# STM32.net
KiCad netlist of a schematic drawn in Altium Designer
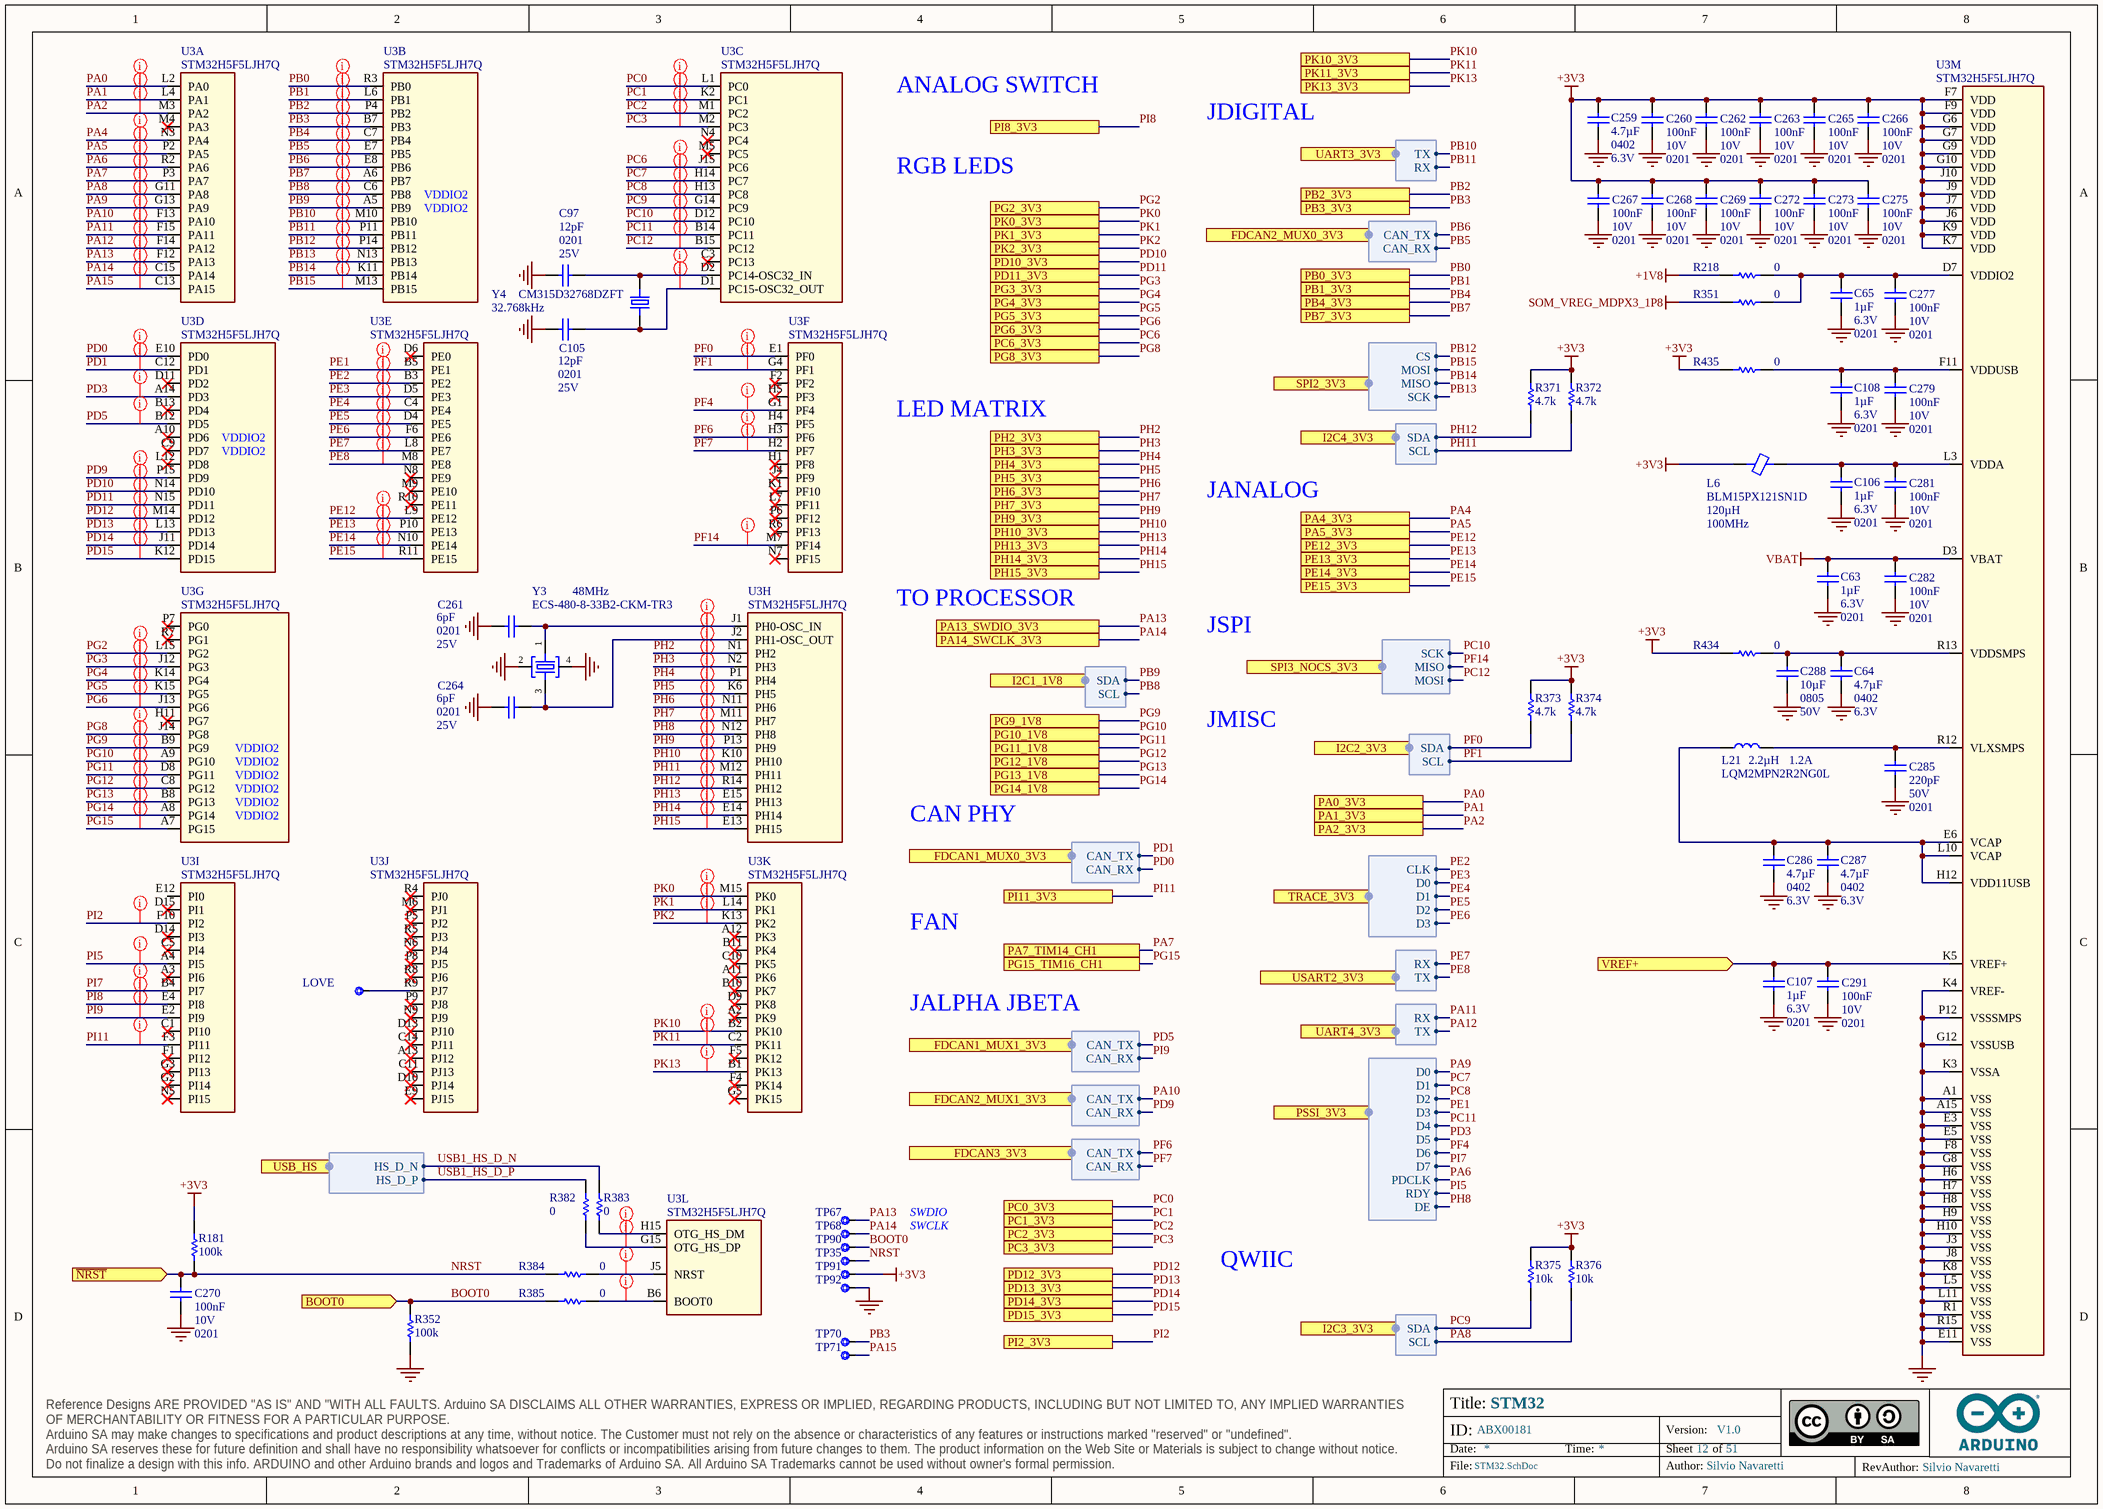
[diagram p0: STM32.SchDoc]

(export (version "E")
  (design (tool "Eeschema 10.0.6"))
  (components
    (comp (ref "C63")
      (value "1µF")
      (footprint "CAP-0201")
      (description "CAP CHIP 0201 1uF 20% 6.3V X5R")
      (fields
        (field (name "VOLTAGE") "6.3V")
        (field (name "TOLERANCE") "20%")
        (field (name "PART NUMBER") "GRM033R60J105MEA2D")
        (field (name "CASE CODE (IMPERIAL)") "0201")
      )
      (libsource (lib "Clean") (part "CAP"))
    )
    (comp (ref "C64")
      (value "4.7µF")
      (footprint "CAP-0402")
      (description "CAP CHIP 0402 4.7uF 20% 6V3 X5R")
      (fields
        (field (name "MANUFACTURER") "Hottech")
        (field (name "PART NUMBER") "C1005A475M6R3NT")
        (field (name "CASE CODE (IMPERIAL)") "0402")
        (field (name "VOLTAGE") "6.3V")
      )
      (libsource (lib "Clean") (part "CAP"))
    )
    (comp (ref "C65")
      (value "1µF")
      (footprint "CAP-0201")
      (description "CAP CHIP 0201 1uF 20% 6.3V X5R")
      (fields
        (field (name "VOLTAGE") "6.3V")
        (field (name "TOLERANCE") "20%")
        (field (name "PART NUMBER") "GRM033R60J105MEA2D")
        (field (name "CASE CODE (IMPERIAL)") "0201")
      )
      (libsource (lib "Clean") (part "CAP"))
    )
    (comp (ref "C97")
      (value "12pF")
      (footprint "CAP-0201")
      (description "CAP CHIP 0201 12pF 5% 25V C0G")
      (fields
        (field (name "CASE CODE (IMPERIAL)") "0201")
        (field (name "PART NUMBER") "GRM0335C1E120JA01J")
        (field (name "VOLTAGE") "25V")
        (field (name "TOLERANCE") "5%")
      )
      (libsource (lib "Clean") (part "CAP"))
    )
    (comp (ref "C105")
      (value "12pF")
      (footprint "CAP-0201")
      (description "CAP CHIP 0201 12pF 5% 25V C0G")
      (fields
        (field (name "CASE CODE (IMPERIAL)") "0201")
        (field (name "PART NUMBER") "GRM0335C1E120JA01J")
        (field (name "VOLTAGE") "25V")
        (field (name "TOLERANCE") "5%")
      )
      (libsource (lib "Clean") (part "CAP"))
    )
    (comp (ref "C106")
      (value "1µF")
      (footprint "CAP-0201")
      (description "CAP CHIP 0201 1uF 20% 6.3V X5R")
      (fields
        (field (name "VOLTAGE") "6.3V")
        (field (name "TOLERANCE") "20%")
        (field (name "PART NUMBER") "GRM033R60J105MEA2D")
        (field (name "CASE CODE (IMPERIAL)") "0201")
      )
      (libsource (lib "Clean") (part "CAP"))
    )
    (comp (ref "C107")
      (value "1µF")
      (footprint "CAP-0201")
      (description "CAP CHIP 0201 1uF 20% 6.3V X5R")
      (fields
        (field (name "VOLTAGE") "6.3V")
        (field (name "TOLERANCE") "20%")
        (field (name "PART NUMBER") "GRM033R60J105MEA2D")
        (field (name "CASE CODE (IMPERIAL)") "0201")
      )
      (libsource (lib "Clean") (part "CAP"))
    )
    (comp (ref "C108")
      (value "1µF")
      (footprint "CAP-0201")
      (description "CAP CHIP 0201 1uF 20% 6.3V X5R")
      (fields
        (field (name "VOLTAGE") "6.3V")
        (field (name "TOLERANCE") "20%")
        (field (name "PART NUMBER") "GRM033R60J105MEA2D")
        (field (name "CASE CODE (IMPERIAL)") "0201")
      )
      (libsource (lib "Clean") (part "CAP"))
    )
    (comp (ref "C259")
      (value "4.7µF")
      (footprint "CAP-0402")
      (description "CAP CHIP 0402 4.7uF 20% 6V3 X5R")
      (fields
        (field (name "MANUFACTURER") "Hottech")
        (field (name "PART NUMBER") "C1005A475M6R3NT")
        (field (name "CASE CODE (IMPERIAL)") "0402")
        (field (name "VOLTAGE") "6.3V")
      )
      (libsource (lib "Clean") (part "CAP"))
    )
    (comp (ref "C260")
      (value "100nF")
      (footprint "CAP-0201")
      (description "CAP CHIP 0201 100nF 10% 10V X5R")
      (fields
        (field (name "PART NUMBER") "CL03A104KP3NNNC")
        (field (name "MANUFACTURER") "Samsung Electro-Mechanics")
        (field (name "VOLTAGE") "10V")
        (field (name "CASE CODE (IMPERIAL)") "0201")
      )
      (libsource (lib "Clean") (part "CAP"))
    )
    (comp (ref "C261")
      (value "6pF")
      (footprint "CAP-0201")
      (description "CAP CHIP 0201 6pF 0.25pF 25V C0G")
      (fields
        (field (name "CASE CODE (IMPERIAL)") "0201")
        (field (name "PART NUMBER") "GRM0335C1E6R0CA01D")
        (field (name "VOLTAGE") "25V")
        (field (name "TOLERANCE") "0.25pF")
      )
      (libsource (lib "Clean") (part "CAP"))
    )
    (comp (ref "C262")
      (value "100nF")
      (footprint "CAP-0201")
      (description "CAP CHIP 0201 100nF 10% 10V X5R")
      (fields
        (field (name "PART NUMBER") "CL03A104KP3NNNC")
        (field (name "MANUFACTURER") "Samsung Electro-Mechanics")
        (field (name "VOLTAGE") "10V")
        (field (name "CASE CODE (IMPERIAL)") "0201")
      )
      (libsource (lib "Clean") (part "CAP"))
    )
    (comp (ref "C263")
      (value "100nF")
      (footprint "CAP-0201")
      (description "CAP CHIP 0201 100nF 10% 10V X5R")
      (fields
        (field (name "PART NUMBER") "CL03A104KP3NNNC")
        (field (name "MANUFACTURER") "Samsung Electro-Mechanics")
        (field (name "VOLTAGE") "10V")
        (field (name "CASE CODE (IMPERIAL)") "0201")
      )
      (libsource (lib "Clean") (part "CAP"))
    )
    (comp (ref "C264")
      (value "6pF")
      (footprint "CAP-0201")
      (description "CAP CHIP 0201 6pF 0.25pF 25V C0G")
      (fields
        (field (name "CASE CODE (IMPERIAL)") "0201")
        (field (name "PART NUMBER") "GRM0335C1E6R0CA01D")
        (field (name "VOLTAGE") "25V")
        (field (name "TOLERANCE") "0.25pF")
      )
      (libsource (lib "Clean") (part "CAP"))
    )
    (comp (ref "C265")
      (value "100nF")
      (footprint "CAP-0201")
      (description "CAP CHIP 0201 100nF 10% 10V X5R")
      (fields
        (field (name "PART NUMBER") "CL03A104KP3NNNC")
        (field (name "MANUFACTURER") "Samsung Electro-Mechanics")
        (field (name "VOLTAGE") "10V")
        (field (name "CASE CODE (IMPERIAL)") "0201")
      )
      (libsource (lib "Clean") (part "CAP"))
    )
    (comp (ref "C266")
      (value "100nF")
      (footprint "CAP-0201")
      (description "CAP CHIP 0201 100nF 10% 10V X5R")
      (fields
        (field (name "PART NUMBER") "CL03A104KP3NNNC")
        (field (name "MANUFACTURER") "Samsung Electro-Mechanics")
        (field (name "VOLTAGE") "10V")
        (field (name "CASE CODE (IMPERIAL)") "0201")
      )
      (libsource (lib "Clean") (part "CAP"))
    )
    (comp (ref "C267")
      (value "100nF")
      (footprint "CAP-0201")
      (description "CAP CHIP 0201 100nF 10% 10V X5R")
      (fields
        (field (name "PART NUMBER") "CL03A104KP3NNNC")
        (field (name "MANUFACTURER") "Samsung Electro-Mechanics")
        (field (name "VOLTAGE") "10V")
        (field (name "CASE CODE (IMPERIAL)") "0201")
      )
      (libsource (lib "Clean") (part "CAP"))
    )
    (comp (ref "C268")
      (value "100nF")
      (footprint "CAP-0201")
      (description "CAP CHIP 0201 100nF 10% 10V X5R")
      (fields
        (field (name "PART NUMBER") "CL03A104KP3NNNC")
        (field (name "MANUFACTURER") "Samsung Electro-Mechanics")
        (field (name "VOLTAGE") "10V")
        (field (name "CASE CODE (IMPERIAL)") "0201")
      )
      (libsource (lib "Clean") (part "CAP"))
    )
    (comp (ref "C269")
      (value "100nF")
      (footprint "CAP-0201")
      (description "CAP CHIP 0201 100nF 10% 10V X5R")
      (fields
        (field (name "PART NUMBER") "CL03A104KP3NNNC")
        (field (name "MANUFACTURER") "Samsung Electro-Mechanics")
        (field (name "VOLTAGE") "10V")
        (field (name "CASE CODE (IMPERIAL)") "0201")
      )
      (libsource (lib "Clean") (part "CAP"))
    )
    (comp (ref "C270")
      (value "100nF")
      (footprint "CAP-0201")
      (description "CAP CHIP 0201 100nF 10% 10V X5R")
      (fields
        (field (name "PART NUMBER") "CL03A104KP3NNNC")
        (field (name "MANUFACTURER") "Samsung Electro-Mechanics")
        (field (name "VOLTAGE") "10V")
        (field (name "CASE CODE (IMPERIAL)") "0201")
      )
      (libsource (lib "Clean") (part "CAP"))
    )
    (comp (ref "C272")
      (value "100nF")
      (footprint "CAP-0201")
      (description "CAP CHIP 0201 100nF 10% 10V X5R")
      (fields
        (field (name "PART NUMBER") "CL03A104KP3NNNC")
        (field (name "MANUFACTURER") "Samsung Electro-Mechanics")
        (field (name "VOLTAGE") "10V")
        (field (name "CASE CODE (IMPERIAL)") "0201")
      )
      (libsource (lib "Clean") (part "CAP"))
    )
    (comp (ref "C273")
      (value "100nF")
      (footprint "CAP-0201")
      (description "CAP CHIP 0201 100nF 10% 10V X5R")
      (fields
        (field (name "PART NUMBER") "CL03A104KP3NNNC")
        (field (name "MANUFACTURER") "Samsung Electro-Mechanics")
        (field (name "VOLTAGE") "10V")
        (field (name "CASE CODE (IMPERIAL)") "0201")
      )
      (libsource (lib "Clean") (part "CAP"))
    )
    (comp (ref "C275")
      (value "100nF")
      (footprint "CAP-0201")
      (description "CAP CHIP 0201 100nF 10% 10V X5R")
      (fields
        (field (name "PART NUMBER") "CL03A104KP3NNNC")
        (field (name "MANUFACTURER") "Samsung Electro-Mechanics")
        (field (name "VOLTAGE") "10V")
        (field (name "CASE CODE (IMPERIAL)") "0201")
      )
      (libsource (lib "Clean") (part "CAP"))
    )
    (comp (ref "C277")
      (value "100nF")
      (footprint "CAP-0201")
      (description "CAP CHIP 0201 100nF 10% 10V X5R")
      (fields
        (field (name "PART NUMBER") "CL03A104KP3NNNC")
        (field (name "MANUFACTURER") "Samsung Electro-Mechanics")
        (field (name "VOLTAGE") "10V")
        (field (name "CASE CODE (IMPERIAL)") "0201")
      )
      (libsource (lib "Clean") (part "CAP"))
    )
    (comp (ref "C279")
      (value "100nF")
      (footprint "CAP-0201")
      (description "CAP CHIP 0201 100nF 10% 10V X5R")
      (fields
        (field (name "PART NUMBER") "CL03A104KP3NNNC")
        (field (name "MANUFACTURER") "Samsung Electro-Mechanics")
        (field (name "VOLTAGE") "10V")
        (field (name "CASE CODE (IMPERIAL)") "0201")
      )
      (libsource (lib "Clean") (part "CAP"))
    )
    (comp (ref "C281")
      (value "100nF")
      (footprint "CAP-0201")
      (description "CAP CHIP 0201 100nF 10% 10V X5R")
      (fields
        (field (name "PART NUMBER") "CL03A104KP3NNNC")
        (field (name "MANUFACTURER") "Samsung Electro-Mechanics")
        (field (name "VOLTAGE") "10V")
        (field (name "CASE CODE (IMPERIAL)") "0201")
      )
      (libsource (lib "Clean") (part "CAP"))
    )
    (comp (ref "C282")
      (value "100nF")
      (footprint "CAP-0201")
      (description "CAP CHIP 0201 100nF 10% 10V X5R")
      (fields
        (field (name "PART NUMBER") "CL03A104KP3NNNC")
        (field (name "MANUFACTURER") "Samsung Electro-Mechanics")
        (field (name "VOLTAGE") "10V")
        (field (name "CASE CODE (IMPERIAL)") "0201")
      )
      (libsource (lib "Clean") (part "CAP"))
    )
    (comp (ref "C285")
      (value "220pF")
      (footprint "CAP-0201")
      (description "CAP CHIP 0201 220pF 10% 50V X7R")
      (fields
        (field (name "PART NUMBER") "GRM033R71H221KA12D")
        (field (name "MANUFACTURER") "Murata")
        (field (name "VOLTAGE") "50V")
        (field (name "CASE CODE (IMPERIAL)") "0201")
      )
      (libsource (lib "Clean") (part "CAP"))
    )
    (comp (ref "C286")
      (value "4.7µF")
      (footprint "CAP-0402")
      (description "CAP CHIP 0402 4.7uF 20% 6V3 X5R")
      (fields
        (field (name "MANUFACTURER") "Hottech")
        (field (name "PART NUMBER") "C1005A475M6R3NT")
        (field (name "CASE CODE (IMPERIAL)") "0402")
        (field (name "VOLTAGE") "6.3V")
      )
      (libsource (lib "Clean") (part "CAP"))
    )
    (comp (ref "C287")
      (value "4.7µF")
      (footprint "CAP-0402")
      (description "CAP CHIP 0402 4.7uF 20% 6V3 X5R")
      (fields
        (field (name "MANUFACTURER") "Hottech")
        (field (name "PART NUMBER") "C1005A475M6R3NT")
        (field (name "CASE CODE (IMPERIAL)") "0402")
        (field (name "VOLTAGE") "6.3V")
      )
      (libsource (lib "Clean") (part "CAP"))
    )
    (comp (ref "C288")
      (value "10µF")
      (footprint "CAP-0805")
      (description "CAP CHIP 0805 10uF 20% 50V X5R")
      (fields
        (field (name "CASE CODE (IMPERIAL)") "0805")
        (field (name "TOLERANCE") "20%")
        (field (name "PART NUMBER") "GRM21BR61H106ME43L")
        (field (name "VOLTAGE") "50V")
      )
      (libsource (lib "Clean") (part "CAP"))
    )
    (comp (ref "C291")
      (value "100nF")
      (footprint "CAP-0201")
      (description "CAP CHIP 0201 100nF 10% 10V X5R")
      (fields
        (field (name "PART NUMBER") "CL03A104KP3NNNC")
        (field (name "MANUFACTURER") "Samsung Electro-Mechanics")
        (field (name "VOLTAGE") "10V")
        (field (name "CASE CODE (IMPERIAL)") "0201")
      )
      (libsource (lib "Clean") (part "CAP"))
    )
    (comp (ref "L6")
      (value "BLM15PX121SN1D")
      (footprint "L-0402")
      (description "FERRITE SMD 0402 120Ohm 25% 100MHz Ferrite 2A")
      (fields
        (field (name "INDUCTANCE") "120µH")
        (field (name "TEST FREQUENCY") "100MHz")
        (field (name "MANUFACTURER") "Murata")
        (field (name "TOLERANCE") "25%")
      )
      (libsource (lib "Clean") (part "Ferrite"))
    )
    (comp (ref "L21")
      (value "LQM2MPN2R2NG0L")
      (footprint "LQM2MPN2R2NG0L")
      (description "INDUCTOR SMD 0806 2.2uH 1.2A")
      (fields
        (field (name "CURRENT") "1.2A")
        (field (name "INDUCTANCE") "2.2µH")
        (field (name "TOLERANCE") "30%")
        (field (name "MANUFACTURER") "Murata")
      )
      (libsource (lib "Clean") (part "Inductor"))
    )
    (comp (ref "LOVE")
      (value "Test point 1.00mm")
      (footprint "TP-1.00MM")
      (fields (field (name "MANUFACTURER") "This is not a component"))
      (libsource (lib "Clean") (part "TESTPOINT"))
    )
    (comp (ref "R181")
      (value "100k")
      (footprint "RES-0201")
      (description "RES CHIP 0201 100k 1% 1/20W")
      (fields (field (name "POWER") "50mW") (field (name "TOLERANCE") "1%"))
      (libsource (lib "Clean") (part "RES"))
    )
    (comp (ref "R218")
      (value "0")
      (footprint "RES-0201")
      (description "RES CHIP 0201 0R")
      (fields (field (name "MANUFACTURER") "Vishay") (field (name "PART NUMBER") "CRCW02010000Z0ED"))
      (libsource (lib "Clean") (part "RES"))
    )
    (comp (ref "R351")
      (value "0")
      (footprint "RES-0201")
      (description "RES CHIP 0201 0R")
      (fields (field (name "MANUFACTURER") "Vishay") (field (name "PART NUMBER") "CRCW02010000Z0ED"))
      (libsource (lib "Clean") (part "RES"))
    )
    (comp (ref "R352")
      (value "100k")
      (footprint "RES-0201")
      (description "RES CHIP 0201 100k 1% 1/20W")
      (fields (field (name "POWER") "50mW") (field (name "TOLERANCE") "1%"))
      (libsource (lib "Clean") (part "RES"))
    )
    (comp (ref "R371")
      (value "4.7k")
      (footprint "RES-0201")
      (description "RES CHIP 0201 4k7 1% 1/20W")
      (fields (field (name "POWER") "50mW") (field (name "TOLERANCE") "1%"))
      (libsource (lib "Clean") (part "RES"))
    )
    (comp (ref "R372")
      (value "4.7k")
      (footprint "RES-0201")
      (description "RES CHIP 0201 4k7 1% 1/20W")
      (fields (field (name "POWER") "50mW") (field (name "TOLERANCE") "1%"))
      (libsource (lib "Clean") (part "RES"))
    )
    (comp (ref "R373")
      (value "4.7k")
      (footprint "RES-0201")
      (description "RES CHIP 0201 4k7 1% 1/20W")
      (fields (field (name "POWER") "50mW") (field (name "TOLERANCE") "1%"))
      (libsource (lib "Clean") (part "RES"))
    )
    (comp (ref "R374")
      (value "4.7k")
      (footprint "RES-0201")
      (description "RES CHIP 0201 4k7 1% 1/20W")
      (fields (field (name "POWER") "50mW") (field (name "TOLERANCE") "1%"))
      (libsource (lib "Clean") (part "RES"))
    )
    (comp (ref "R375")
      (value "10k")
      (footprint "RES-0201")
      (description "RES CHIP 0201 10k 1% 1/20W")
      (fields (field (name "POWER") "50mW") (field (name "TOLERANCE") "1%"))
      (libsource (lib "Clean") (part "RES"))
    )
    (comp (ref "R376")
      (value "10k")
      (footprint "RES-0201")
      (description "RES CHIP 0201 10k 1% 1/20W")
      (fields (field (name "POWER") "50mW") (field (name "TOLERANCE") "1%"))
      (libsource (lib "Clean") (part "RES"))
    )
    (comp (ref "R382")
      (value "0")
      (footprint "RES-0201")
      (description "RES CHIP 0201 0R")
      (fields (field (name "MANUFACTURER") "Vishay") (field (name "PART NUMBER") "CRCW02010000Z0ED"))
      (libsource (lib "Clean") (part "RES"))
    )
    (comp (ref "R383")
      (value "0")
      (footprint "RES-0201")
      (description "RES CHIP 0201 0R")
      (fields (field (name "MANUFACTURER") "Vishay") (field (name "PART NUMBER") "CRCW02010000Z0ED"))
      (libsource (lib "Clean") (part "RES"))
    )
    (comp (ref "R384")
      (value "0")
      (footprint "RES-0201")
      (description "RES CHIP 0201 0R")
      (fields (field (name "MANUFACTURER") "Vishay") (field (name "PART NUMBER") "CRCW02010000Z0ED"))
      (libsource (lib "Clean") (part "RES"))
    )
    (comp (ref "R385")
      (value "0")
      (footprint "RES-0201")
      (description "RES CHIP 0201 0R")
      (fields (field (name "MANUFACTURER") "Vishay") (field (name "PART NUMBER") "CRCW02010000Z0ED"))
      (libsource (lib "Clean") (part "RES"))
    )
    (comp (ref "R434")
      (value "0")
      (footprint "RES-0201")
      (description "RES CHIP 0201 0R")
      (fields (field (name "MANUFACTURER") "Vishay") (field (name "PART NUMBER") "CRCW02010000Z0ED"))
      (libsource (lib "Clean") (part "RES"))
    )
    (comp (ref "R435")
      (value "0")
      (footprint "RES-0201")
      (description "RES CHIP 0201 0R")
      (fields (field (name "MANUFACTURER") "Vishay") (field (name "PART NUMBER") "CRCW02010000Z0ED"))
      (libsource (lib "Clean") (part "RES"))
    )
    (comp (ref "TP35")
      (value "Test point 1.00mm")
      (footprint "TP-1.00MM")
      (fields (field (name "PART NUMBER") "This is not a component"))
      (libsource (lib "Clean") (part "TESTPOINT"))
    )
    (comp (ref "TP67")
      (value "Test point 1.00mm")
      (footprint "TP-1.00MM")
      (fields (field (name "PART NUMBER") "This is not a component"))
      (libsource (lib "Clean") (part "TESTPOINT"))
    )
    (comp (ref "TP68")
      (value "Test point 1.00mm")
      (footprint "TP-1.00MM")
      (fields (field (name "PART NUMBER") "This is not a component"))
      (libsource (lib "Clean") (part "TESTPOINT"))
    )
    (comp (ref "TP70")
      (value "Test point 1.00mm")
      (footprint "TP-1.00MM")
      (fields (field (name "PART NUMBER") "This is not a component"))
      (libsource (lib "Clean") (part "TESTPOINT"))
    )
    (comp (ref "TP71")
      (value "Test point 1.00mm")
      (footprint "TP-1.00MM")
      (fields (field (name "PART NUMBER") "This is not a component"))
      (libsource (lib "Clean") (part "TESTPOINT"))
    )
    (comp (ref "TP90")
      (value "Test point 1.00mm")
      (footprint "TP-1.00MM")
      (fields (field (name "PART NUMBER") "This is not a component"))
      (libsource (lib "Clean") (part "TESTPOINT"))
    )
    (comp (ref "TP91")
      (value "Test point 1.00mm")
      (footprint "TP-1.00MM")
      (fields (field (name "PART NUMBER") "This is not a component"))
      (libsource (lib "Clean") (part "TESTPOINT"))
    )
    (comp (ref "TP92")
      (value "Test point 1.00mm")
      (footprint "TP-1.00MM")
      (fields (field (name "PART NUMBER") "This is not a component"))
      (libsource (lib "Clean") (part "TESTPOINT"))
    )
    (comp (ref "U3")
      (value "STM32H5F5LJH7Q")
      (footprint "BGA225C80P15X15_1300X1300X120")
      (description "IC Cortex M33 250MHz, 4MB flash, 1.5MB RAM, TFBGA225 13x13mm")
      (fields (field (name "MANUFACTURER") "ST"))
      (libsource (lib "Clean") (part "STM32H5F5LJH7Q"))
    )
    (comp (ref "Y3")
      (value "ECS-480-8-33B2-CKM-TR3")
      (footprint "CRYSTAL3.2X2.5")
      (description "CRYSTAL 48MHz tolerance 10ppm stability 15ppm load 10pF, shunt 2pF, ESR 30R, 3.2x2.5mm")
      (fields (field (name "FREQUENCY") "48MHz") (field (name "MANUFACTURER") "ECS"))
      (libsource (lib "Clean") (part "Crystal"))
    )
    (comp (ref "Y4")
      (value "CM315D32768DZFT")
      (footprint "ABS07")
      (description "CRYSTAL 32.768kHz 20ppm 12.5pF SMD 1.6x0.9mm")
      (fields (field (name "FREQUENCY") "32.768kHz") (field (name "MANUFACTURER") "Citizen FineDevice"))
      (libsource (lib "") (part "Crystal_1"))
    )
  )
  (nets
    (net (code "9") (name "+1V8") (class "Default")
      (node (ref "R218") (pin "1") (pinfunction "1_1") (pintype "passive"))
    )
    (net (code "10") (name "+3V3") (class "Default")
      (node (ref "C259") (pin "1") (pinfunction "1_1") (pintype "passive"))
      (node (ref "C260") (pin "2") (pinfunction "2_2") (pintype "passive"))
      (node (ref "C262") (pin "2") (pinfunction "2_2") (pintype "passive"))
      (node (ref "C263") (pin "2") (pinfunction "2_2") (pintype "passive"))
      (node (ref "C265") (pin "2") (pinfunction "2_2") (pintype "passive"))
      (node (ref "C266") (pin "2") (pinfunction "2_2") (pintype "passive"))
      (node (ref "C267") (pin "2") (pinfunction "2_2") (pintype "passive"))
      (node (ref "C268") (pin "2") (pinfunction "2_2") (pintype "passive"))
      (node (ref "C269") (pin "2") (pinfunction "2_2") (pintype "passive"))
      (node (ref "C272") (pin "2") (pinfunction "2_2") (pintype "passive"))
      (node (ref "C273") (pin "2") (pinfunction "2_2") (pintype "passive"))
      (node (ref "C275") (pin "2") (pinfunction "2_2") (pintype "passive"))
      (node (ref "L6") (pin "1") (pinfunction "1_1") (pintype "passive"))
      (node (ref "R181") (pin "2") (pinfunction "2_2") (pintype "passive"))
      (node (ref "R371") (pin "2") (pinfunction "2_2") (pintype "passive"))
      (node (ref "R372") (pin "2") (pinfunction "2_2") (pintype "passive"))
      (node (ref "R373") (pin "2") (pinfunction "2_2") (pintype "passive"))
      (node (ref "R374") (pin "2") (pinfunction "2_2") (pintype "passive"))
      (node (ref "R375") (pin "2") (pinfunction "2_2") (pintype "passive"))
      (node (ref "R376") (pin "2") (pinfunction "2_2") (pintype "passive"))
      (node (ref "R434") (pin "1") (pinfunction "1_1") (pintype "passive"))
      (node (ref "R435") (pin "1") (pinfunction "1_1") (pintype "passive"))
      (node (ref "TP91") (pin "X") (pinfunction "X_X") (pintype "passive"))
      (node (ref "U3") (pin "F7") (pinfunction "VDD_F7") (pintype "passive"))
      (node (ref "U3") (pin "F9") (pinfunction "VDD_F9") (pintype "passive"))
      (node (ref "U3") (pin "G10") (pinfunction "VDD_G10") (pintype "passive"))
      (node (ref "U3") (pin "G6") (pinfunction "VDD_G6") (pintype "passive"))
      (node (ref "U3") (pin "G7") (pinfunction "VDD_G7") (pintype "passive"))
      (node (ref "U3") (pin "G9") (pinfunction "VDD_G9") (pintype "passive"))
      (node (ref "U3") (pin "J10") (pinfunction "VDD_J10") (pintype "passive"))
      (node (ref "U3") (pin "J6") (pinfunction "VDD_J6") (pintype "passive"))
      (node (ref "U3") (pin "J7") (pinfunction "VDD_J7") (pintype "passive"))
      (node (ref "U3") (pin "J9") (pinfunction "VDD_J9") (pintype "passive"))
      (node (ref "U3") (pin "K7") (pinfunction "VDD_K7") (pintype "passive"))
      (node (ref "U3") (pin "K9") (pinfunction "VDD_K9") (pintype "passive"))
    )
    (net (code "11") (name "/BOOT0") (class "Default")
      (node (ref "R352") (pin "2") (pinfunction "2_2") (pintype "passive"))
      (node (ref "R385") (pin "1") (pinfunction "1_1") (pintype "passive"))
      (node (ref "TP90") (pin "X") (pinfunction "X_X") (pintype "passive"))
    )
    (net (code "12") (name "/NRST") (class "Default")
      (node (ref "C270") (pin "2") (pinfunction "2_2") (pintype "passive"))
      (node (ref "R181") (pin "1") (pinfunction "1_1") (pintype "passive"))
      (node (ref "R384") (pin "1") (pinfunction "1_1") (pintype "passive"))
      (node (ref "TP35") (pin "X") (pinfunction "X_X") (pintype "passive"))
    )
    (net (code "13") (name "/PA0") (class "Default")
      (node (ref "U3") (pin "L2") (pinfunction "PA0_L2") (pintype "passive"))
    )
    (net (code "14") (name "/PA1") (class "Default")
      (node (ref "U3") (pin "L4") (pinfunction "PA1_L4") (pintype "passive"))
    )
    (net (code "15") (name "/PA2") (class "Default")
      (node (ref "U3") (pin "M3") (pinfunction "PA2_M3") (pintype "passive"))
    )
    (net (code "16") (name "/PA4") (class "Default")
      (node (ref "U3") (pin "N3") (pinfunction "PA4_N3") (pintype "passive"))
    )
    (net (code "17") (name "/PA5") (class "Default")
      (node (ref "U3") (pin "P2") (pinfunction "PA5_P2") (pintype "passive"))
    )
    (net (code "18") (name "/PA6") (class "Default")
      (node (ref "U3") (pin "R2") (pinfunction "PA6_R2") (pintype "passive"))
    )
    (net (code "19") (name "/PA7") (class "Default")
      (node (ref "U3") (pin "P3") (pinfunction "PA7_P3") (pintype "passive"))
    )
    (net (code "20") (name "/PA8") (class "Default")
      (node (ref "R376") (pin "1") (pinfunction "1_1") (pintype "passive"))
      (node (ref "U3") (pin "G11") (pinfunction "PA8_G11") (pintype "passive"))
    )
    (net (code "21") (name "/PA9") (class "Default")
      (node (ref "U3") (pin "G13") (pinfunction "PA9_G13") (pintype "passive"))
    )
    (net (code "22") (name "/PA10") (class "Default")
      (node (ref "U3") (pin "F13") (pinfunction "PA10_F13") (pintype "passive"))
    )
    (net (code "23") (name "/PA11") (class "Default")
      (node (ref "U3") (pin "F15") (pinfunction "PA11_F15") (pintype "passive"))
    )
    (net (code "24") (name "/PA12") (class "Default")
      (node (ref "U3") (pin "F14") (pinfunction "PA12_F14") (pintype "passive"))
    )
    (net (code "25") (name "/PA13") (class "Default")
      (node (ref "TP67") (pin "X") (pinfunction "X_X") (pintype "passive"))
      (node (ref "U3") (pin "F12") (pinfunction "PA13_F12") (pintype "passive"))
    )
    (net (code "26") (name "/PA14") (class "Default")
      (node (ref "TP68") (pin "X") (pinfunction "X_X") (pintype "passive"))
      (node (ref "U3") (pin "C15") (pinfunction "PA14_C15") (pintype "passive"))
    )
    (net (code "27") (name "/PA15") (class "Default")
      (node (ref "TP71") (pin "X") (pinfunction "X_X") (pintype "passive"))
      (node (ref "U3") (pin "C13") (pinfunction "PA15_C13") (pintype "passive"))
    )
    (net (code "28") (name "/PB0") (class "Default")
      (node (ref "U3") (pin "R3") (pinfunction "PB0_R3") (pintype "passive"))
    )
    (net (code "29") (name "/PB1") (class "Default")
      (node (ref "U3") (pin "L6") (pinfunction "PB1_L6") (pintype "passive"))
    )
    (net (code "30") (name "/PB2") (class "Default")
      (node (ref "U3") (pin "P4") (pinfunction "PB2_P4") (pintype "passive"))
    )
    (net (code "31") (name "/PB3") (class "Default")
      (node (ref "TP70") (pin "X") (pinfunction "X_X") (pintype "passive"))
      (node (ref "U3") (pin "B7") (pinfunction "PB3_B7") (pintype "passive"))
    )
    (net (code "32") (name "/PB4") (class "Default")
      (node (ref "U3") (pin "C7") (pinfunction "PB4_C7") (pintype "passive"))
    )
    (net (code "33") (name "/PB5") (class "Default")
      (node (ref "U3") (pin "E7") (pinfunction "PB5_E7") (pintype "passive"))
    )
    (net (code "34") (name "/PB6") (class "Default")
      (node (ref "U3") (pin "E8") (pinfunction "PB6_E8") (pintype "passive"))
    )
    (net (code "35") (name "/PB7") (class "Default")
      (node (ref "U3") (pin "A6") (pinfunction "PB7_A6") (pintype "passive"))
    )
    (net (code "36") (name "/PB8") (class "Default")
      (node (ref "U3") (pin "C6") (pinfunction "PB8_C6") (pintype "passive"))
    )
    (net (code "37") (name "/PB9") (class "Default")
      (node (ref "U3") (pin "A5") (pinfunction "PB9_A5") (pintype "passive"))
    )
    (net (code "38") (name "/PB10") (class "Default")
      (node (ref "U3") (pin "M10") (pinfunction "PB10_M10") (pintype "passive"))
    )
    (net (code "39") (name "/PB11") (class "Default")
      (node (ref "U3") (pin "P11") (pinfunction "PB11_P11") (pintype "passive"))
    )
    (net (code "40") (name "/PB12") (class "Default")
      (node (ref "U3") (pin "P14") (pinfunction "PB12_P14") (pintype "passive"))
    )
    (net (code "41") (name "/PB13") (class "Default")
      (node (ref "U3") (pin "N13") (pinfunction "PB13_N13") (pintype "passive"))
    )
    (net (code "42") (name "/PB14") (class "Default")
      (node (ref "U3") (pin "K11") (pinfunction "PB14_K11") (pintype "passive"))
    )
    (net (code "43") (name "/PB15") (class "Default")
      (node (ref "U3") (pin "M13") (pinfunction "PB15_M13") (pintype "passive"))
    )
    (net (code "44") (name "/PC0") (class "Default")
      (node (ref "U3") (pin "L1") (pinfunction "PC0_L1") (pintype "passive"))
    )
    (net (code "45") (name "/PC1") (class "Default")
      (node (ref "U3") (pin "K2") (pinfunction "PC1_K2") (pintype "passive"))
    )
    (net (code "46") (name "/PC2") (class "Default")
      (node (ref "U3") (pin "M1") (pinfunction "PC2_M1") (pintype "passive"))
    )
    (net (code "47") (name "/PC3") (class "Default")
      (node (ref "U3") (pin "M2") (pinfunction "PC3_M2") (pintype "passive"))
    )
    (net (code "48") (name "/PC6") (class "Default")
      (node (ref "U3") (pin "J15") (pinfunction "PC6_J15") (pintype "passive"))
    )
    (net (code "49") (name "/PC7") (class "Default")
      (node (ref "U3") (pin "H14") (pinfunction "PC7_H14") (pintype "passive"))
    )
    (net (code "50") (name "/PC8") (class "Default")
      (node (ref "U3") (pin "H13") (pinfunction "PC8_H13") (pintype "passive"))
    )
    (net (code "51") (name "/PC9") (class "Default")
      (node (ref "R375") (pin "1") (pinfunction "1_1") (pintype "passive"))
      (node (ref "U3") (pin "G14") (pinfunction "PC9_G14") (pintype "passive"))
    )
    (net (code "52") (name "/PC10") (class "Default")
      (node (ref "U3") (pin "D12") (pinfunction "PC10_D12") (pintype "passive"))
    )
    (net (code "53") (name "/PC11") (class "Default")
      (node (ref "U3") (pin "B14") (pinfunction "PC11_B14") (pintype "passive"))
    )
    (net (code "54") (name "/PC12") (class "Default")
      (node (ref "U3") (pin "B15") (pinfunction "PC12_B15") (pintype "passive"))
    )
    (net (code "55") (name "/PD0") (class "Default")
      (node (ref "U3") (pin "E10") (pinfunction "PD0_E10") (pintype "passive"))
    )
    (net (code "56") (name "/PD1") (class "Default")
      (node (ref "U3") (pin "C12") (pinfunction "PD1_C12") (pintype "passive"))
    )
    (net (code "57") (name "/PD3") (class "Default")
      (node (ref "U3") (pin "A14") (pinfunction "PD3_A14") (pintype "passive"))
    )
    (net (code "58") (name "/PD5") (class "Default")
      (node (ref "U3") (pin "B12") (pinfunction "PD5_B12") (pintype "passive"))
    )
    (net (code "59") (name "/PD9") (class "Default")
      (node (ref "U3") (pin "P15") (pinfunction "PD9_P15") (pintype "passive"))
    )
    (net (code "60") (name "/PD10") (class "Default")
      (node (ref "U3") (pin "N14") (pinfunction "PD10_N14") (pintype "passive"))
    )
    (net (code "61") (name "/PD11") (class "Default")
      (node (ref "U3") (pin "N15") (pinfunction "PD11_N15") (pintype "passive"))
    )
    (net (code "62") (name "/PD12") (class "Default")
      (node (ref "U3") (pin "M14") (pinfunction "PD12_M14") (pintype "passive"))
    )
    (net (code "63") (name "/PD13") (class "Default")
      (node (ref "U3") (pin "L13") (pinfunction "PD13_L13") (pintype "passive"))
    )
    (net (code "64") (name "/PD14") (class "Default")
      (node (ref "U3") (pin "J11") (pinfunction "PD14_J11") (pintype "passive"))
    )
    (net (code "65") (name "/PD15") (class "Default")
      (node (ref "U3") (pin "K12") (pinfunction "PD15_K12") (pintype "passive"))
    )
    (net (code "66") (name "/PE1") (class "Default")
      (node (ref "U3") (pin "B5") (pinfunction "PE1_B5") (pintype "passive"))
    )
    (net (code "67") (name "/PE2") (class "Default")
      (node (ref "U3") (pin "B3") (pinfunction "PE2_B3") (pintype "passive"))
    )
    (net (code "68") (name "/PE3") (class "Default")
      (node (ref "U3") (pin "D5") (pinfunction "PE3_D5") (pintype "passive"))
    )
    (net (code "69") (name "/PE4") (class "Default")
      (node (ref "U3") (pin "C4") (pinfunction "PE4_C4") (pintype "passive"))
    )
    (net (code "70") (name "/PE5") (class "Default")
      (node (ref "U3") (pin "D4") (pinfunction "PE5_D4") (pintype "passive"))
    )
    (net (code "71") (name "/PE6") (class "Default")
      (node (ref "U3") (pin "F6") (pinfunction "PE6_F6") (pintype "passive"))
    )
    (net (code "72") (name "/PE7") (class "Default")
      (node (ref "U3") (pin "L8") (pinfunction "PE7_L8") (pintype "passive"))
    )
    (net (code "73") (name "/PE8") (class "Default")
      (node (ref "U3") (pin "M8") (pinfunction "PE8_M8") (pintype "passive"))
    )
    (net (code "74") (name "/PE12") (class "Default")
      (node (ref "U3") (pin "L9") (pinfunction "PE12_L9") (pintype "passive"))
    )
    (net (code "75") (name "/PE13") (class "Default")
      (node (ref "U3") (pin "P10") (pinfunction "PE13_P10") (pintype "passive"))
    )
    (net (code "76") (name "/PE14") (class "Default")
      (node (ref "U3") (pin "N10") (pinfunction "PE14_N10") (pintype "passive"))
    )
    (net (code "77") (name "/PE15") (class "Default")
      (node (ref "U3") (pin "R11") (pinfunction "PE15_R11") (pintype "passive"))
    )
    (net (code "78") (name "/PF0") (class "Default")
      (node (ref "R373") (pin "1") (pinfunction "1_1") (pintype "passive"))
      (node (ref "U3") (pin "E1") (pinfunction "PF0_E1") (pintype "passive"))
    )
    (net (code "79") (name "/PF1") (class "Default")
      (node (ref "R374") (pin "1") (pinfunction "1_1") (pintype "passive"))
      (node (ref "U3") (pin "G4") (pinfunction "PF1_G4") (pintype "passive"))
    )
    (net (code "80") (name "/PF4") (class "Default")
      (node (ref "U3") (pin "G1") (pinfunction "PF4_G1") (pintype "passive"))
    )
    (net (code "81") (name "/PF6") (class "Default")
      (node (ref "U3") (pin "H3") (pinfunction "PF6_H3") (pintype "passive"))
    )
    (net (code "82") (name "/PF7") (class "Default")
      (node (ref "U3") (pin "H2") (pinfunction "PF7_H2") (pintype "passive"))
    )
    (net (code "83") (name "/PF14") (class "Default")
      (node (ref "U3") (pin "M7") (pinfunction "PF14_M7") (pintype "passive"))
    )
    (net (code "84") (name "/PG2") (class "Default")
      (node (ref "U3") (pin "L15") (pinfunction "PG2_L15") (pintype "passive"))
    )
    (net (code "85") (name "/PG3") (class "Default")
      (node (ref "U3") (pin "J12") (pinfunction "PG3_J12") (pintype "passive"))
    )
    (net (code "86") (name "/PG4") (class "Default")
      (node (ref "U3") (pin "K14") (pinfunction "PG4_K14") (pintype "passive"))
    )
    (net (code "87") (name "/PG5") (class "Default")
      (node (ref "U3") (pin "K15") (pinfunction "PG5_K15") (pintype "passive"))
    )
    (net (code "88") (name "/PG6") (class "Default")
      (node (ref "U3") (pin "J13") (pinfunction "PG6_J13") (pintype "passive"))
    )
    (net (code "89") (name "/PG8") (class "Default")
      (node (ref "U3") (pin "J14") (pinfunction "PG8_J14") (pintype "passive"))
    )
    (net (code "90") (name "/PG9") (class "Default")
      (node (ref "U3") (pin "B9") (pinfunction "PG9_B9") (pintype "passive"))
    )
    (net (code "91") (name "/PG10") (class "Default")
      (node (ref "U3") (pin "A9") (pinfunction "PG10_A9") (pintype "passive"))
    )
    (net (code "92") (name "/PG11") (class "Default")
      (node (ref "U3") (pin "D8") (pinfunction "PG11_D8") (pintype "passive"))
    )
    (net (code "93") (name "/PG12") (class "Default")
      (node (ref "U3") (pin "C8") (pinfunction "PG12_C8") (pintype "passive"))
    )
    (net (code "94") (name "/PG13") (class "Default")
      (node (ref "U3") (pin "B8") (pinfunction "PG13_B8") (pintype "passive"))
    )
    (net (code "95") (name "/PG14") (class "Default")
      (node (ref "U3") (pin "A8") (pinfunction "PG14_A8") (pintype "passive"))
    )
    (net (code "96") (name "/PG15") (class "Default")
      (node (ref "U3") (pin "A7") (pinfunction "PG15_A7") (pintype "passive"))
    )
    (net (code "97") (name "/PH2") (class "Default")
      (node (ref "U3") (pin "N1") (pinfunction "PH2_N1") (pintype "passive"))
    )
    (net (code "98") (name "/PH3") (class "Default")
      (node (ref "U3") (pin "N2") (pinfunction "PH3_N2") (pintype "passive"))
    )
    (net (code "99") (name "/PH4") (class "Default")
      (node (ref "U3") (pin "P1") (pinfunction "PH4_P1") (pintype "passive"))
    )
    (net (code "100") (name "/PH5") (class "Default")
      (node (ref "U3") (pin "K6") (pinfunction "PH5_K6") (pintype "passive"))
    )
    (net (code "101") (name "/PH6") (class "Default")
      (node (ref "U3") (pin "N11") (pinfunction "PH6_N11") (pintype "passive"))
    )
    (net (code "102") (name "/PH7") (class "Default")
      (node (ref "U3") (pin "M11") (pinfunction "PH7_M11") (pintype "passive"))
    )
    (net (code "103") (name "/PH8") (class "Default")
      (node (ref "U3") (pin "N12") (pinfunction "PH8_N12") (pintype "passive"))
    )
    (net (code "104") (name "/PH9") (class "Default")
      (node (ref "U3") (pin "P13") (pinfunction "PH9_P13") (pintype "passive"))
    )
    (net (code "105") (name "/PH10") (class "Default")
      (node (ref "U3") (pin "K10") (pinfunction "PH10_K10") (pintype "passive"))
    )
    (net (code "106") (name "/PH11") (class "Default")
      (node (ref "R372") (pin "1") (pinfunction "1_1") (pintype "passive"))
      (node (ref "U3") (pin "M12") (pinfunction "PH11_M12") (pintype "passive"))
    )
    (net (code "107") (name "/PH12") (class "Default")
      (node (ref "R371") (pin "1") (pinfunction "1_1") (pintype "passive"))
      (node (ref "U3") (pin "R14") (pinfunction "PH12_R14") (pintype "passive"))
    )
    (net (code "108") (name "/PH13") (class "Default")
      (node (ref "U3") (pin "E15") (pinfunction "PH13_E15") (pintype "passive"))
    )
    (net (code "109") (name "/PH14") (class "Default")
      (node (ref "U3") (pin "E14") (pinfunction "PH14_E14") (pintype "passive"))
    )
    (net (code "110") (name "/PH15") (class "Default")
      (node (ref "U3") (pin "E13") (pinfunction "PH15_E13") (pintype "passive"))
    )
    (net (code "111") (name "/PI2") (class "Default")
      (node (ref "U3") (pin "F10") (pinfunction "PI2_F10") (pintype "passive"))
    )
    (net (code "112") (name "/PI5") (class "Default")
      (node (ref "U3") (pin "A4") (pinfunction "PI5_A4") (pintype "passive"))
    )
    (net (code "113") (name "/PI7") (class "Default")
      (node (ref "U3") (pin "B4") (pinfunction "PI7_B4") (pintype "passive"))
    )
    (net (code "114") (name "/PI8") (class "Default")
      (node (ref "U3") (pin "E4") (pinfunction "PI8_E4") (pintype "passive"))
    )
    (net (code "115") (name "/PI9") (class "Default")
      (node (ref "U3") (pin "E2") (pinfunction "PI9_E2") (pintype "passive"))
    )
    (net (code "116") (name "/PI11") (class "Default")
      (node (ref "U3") (pin "F3") (pinfunction "PI11_F3") (pintype "passive"))
    )
    (net (code "117") (name "/PK0") (class "Default")
      (node (ref "U3") (pin "M15") (pinfunction "PK0_M15") (pintype "passive"))
    )
    (net (code "118") (name "/PK1") (class "Default")
      (node (ref "U3") (pin "L14") (pinfunction "PK1_L14") (pintype "passive"))
    )
    (net (code "119") (name "/PK2") (class "Default")
      (node (ref "U3") (pin "K13") (pinfunction "PK2_K13") (pintype "passive"))
    )
    (net (code "120") (name "/PK10") (class "Default")
      (node (ref "U3") (pin "B2") (pinfunction "PK10_B2") (pintype "passive"))
    )
    (net (code "121") (name "/PK11") (class "Default")
      (node (ref "U3") (pin "C2") (pinfunction "PK11_C2") (pintype "passive"))
    )
    (net (code "122") (name "/PK13") (class "Default")
      (node (ref "U3") (pin "B1") (pinfunction "PK13_B1") (pintype "passive"))
    )
    (net (code "123") (name "/USB1_HS_D_N") (class "Default")
      (node (ref "R383") (pin "1") (pinfunction "1_1") (pintype "passive"))
    )
    (net (code "124") (name "/USB1_HS_D_P") (class "Default")
      (node (ref "R382") (pin "1") (pinfunction "1_1") (pintype "passive"))
    )
    (net (code "125") (name "/VREF+") (class "Default")
      (node (ref "C107") (pin "2") (pinfunction "2_2") (pintype "passive"))
      (node (ref "C291") (pin "2") (pinfunction "2_2") (pintype "passive"))
      (node (ref "U3") (pin "K5") (pinfunction "VREF+_K5") (pintype "passive"))
    )
    (net (code "134") (name "GND") (class "Default")
      (node (ref "C105") (pin "2") (pinfunction "2_2") (pintype "passive"))
      (node (ref "C106") (pin "1") (pinfunction "1_1") (pintype "passive"))
      (node (ref "C107") (pin "1") (pinfunction "1_1") (pintype "passive"))
      (node (ref "C108") (pin "1") (pinfunction "1_1") (pintype "passive"))
      (node (ref "C259") (pin "2") (pinfunction "2_2") (pintype "passive"))
      (node (ref "C260") (pin "1") (pinfunction "1_1") (pintype "passive"))
      (node (ref "C261") (pin "2") (pinfunction "2_2") (pintype "passive"))
      (node (ref "C262") (pin "1") (pinfunction "1_1") (pintype "passive"))
      (node (ref "C263") (pin "1") (pinfunction "1_1") (pintype "passive"))
      (node (ref "C264") (pin "2") (pinfunction "2_2") (pintype "passive"))
      (node (ref "C265") (pin "1") (pinfunction "1_1") (pintype "passive"))
      (node (ref "C266") (pin "1") (pinfunction "1_1") (pintype "passive"))
      (node (ref "C267") (pin "1") (pinfunction "1_1") (pintype "passive"))
      (node (ref "C268") (pin "1") (pinfunction "1_1") (pintype "passive"))
      (node (ref "C269") (pin "1") (pinfunction "1_1") (pintype "passive"))
      (node (ref "C270") (pin "1") (pinfunction "1_1") (pintype "passive"))
      (node (ref "C272") (pin "1") (pinfunction "1_1") (pintype "passive"))
      (node (ref "C273") (pin "1") (pinfunction "1_1") (pintype "passive"))
      (node (ref "C275") (pin "1") (pinfunction "1_1") (pintype "passive"))
      (node (ref "C277") (pin "1") (pinfunction "1_1") (pintype "passive"))
      (node (ref "C279") (pin "1") (pinfunction "1_1") (pintype "passive"))
      (node (ref "C281") (pin "1") (pinfunction "1_1") (pintype "passive"))
      (node (ref "C282") (pin "1") (pinfunction "1_1") (pintype "passive"))
      (node (ref "C285") (pin "1") (pinfunction "1_1") (pintype "passive"))
      (node (ref "C286") (pin "2") (pinfunction "2_2") (pintype "passive"))
      (node (ref "C287") (pin "2") (pinfunction "2_2") (pintype "passive"))
      (node (ref "C288") (pin "2") (pinfunction "2_2") (pintype "passive"))
      (node (ref "C291") (pin "1") (pinfunction "1_1") (pintype "passive"))
      (node (ref "C63") (pin "1") (pinfunction "1_1") (pintype "passive"))
      (node (ref "C64") (pin "2") (pinfunction "2_2") (pintype "passive"))
      (node (ref "C65") (pin "1") (pinfunction "1_1") (pintype "passive"))
      (node (ref "C97") (pin "2") (pinfunction "2_2") (pintype "passive"))
      (node (ref "R352") (pin "1") (pinfunction "1_1") (pintype "passive"))
      (node (ref "TP92") (pin "X") (pinfunction "X_X") (pintype "passive"))
      (node (ref "U3") (pin "A1") (pinfunction "VSS_A1") (pintype "passive"))
      (node (ref "U3") (pin "A15") (pinfunction "VSS_A15") (pintype "passive"))
      (node (ref "U3") (pin "E11") (pinfunction "VSS_E11") (pintype "passive"))
      (node (ref "U3") (pin "E3") (pinfunction "VSS_E3") (pintype "passive"))
      (node (ref "U3") (pin "E5") (pinfunction "VSS_E5") (pintype "passive"))
      (node (ref "U3") (pin "F8") (pinfunction "VSS_F8") (pintype "passive"))
      (node (ref "U3") (pin "G12") (pinfunction "VSSUSB_G12") (pintype "passive"))
      (node (ref "U3") (pin "G8") (pinfunction "VSS_G8") (pintype "passive"))
      (node (ref "U3") (pin "H10") (pinfunction "VSS_H10") (pintype "passive"))
      (node (ref "U3") (pin "H6") (pinfunction "VSS_H6") (pintype "passive"))
      (node (ref "U3") (pin "H7") (pinfunction "VSS_H7") (pintype "passive"))
      (node (ref "U3") (pin "H8") (pinfunction "VSS_H8") (pintype "passive"))
      (node (ref "U3") (pin "H9") (pinfunction "VSS_H9") (pintype "passive"))
      (node (ref "U3") (pin "J3") (pinfunction "VSS_J3") (pintype "passive"))
      (node (ref "U3") (pin "J8") (pinfunction "VSS_J8") (pintype "passive"))
      (node (ref "U3") (pin "K3") (pinfunction "VSSA_K3") (pintype "passive"))
      (node (ref "U3") (pin "K4") (pinfunction "VREF-_K4") (pintype "passive"))
      (node (ref "U3") (pin "K8") (pinfunction "VSS_K8") (pintype "passive"))
      (node (ref "U3") (pin "L11") (pinfunction "VSS_L11") (pintype "passive"))
      (node (ref "U3") (pin "L5") (pinfunction "VSS_L5") (pintype "passive"))
      (node (ref "U3") (pin "P12") (pinfunction "VSSSMPS_P12") (pintype "passive"))
      (node (ref "U3") (pin "R1") (pinfunction "VSS_R1") (pintype "passive"))
      (node (ref "U3") (pin "R15") (pinfunction "VSS_R15") (pintype "passive"))
      (node (ref "Y3") (pin "2") (pinfunction "2_2") (pintype "passive"))
      (node (ref "Y3") (pin "4") (pinfunction "4_4") (pintype "passive"))
    )
    (net (code "135") (name "Net-(U3C-PC14-OSC32_IN)") (class "Default")
      (node (ref "C97") (pin "1") (pinfunction "1_1") (pintype "passive"))
      (node (ref "U3") (pin "D2") (pinfunction "PC14-OSC32_IN_D2") (pintype "passive"))
      (node (ref "Y4") (pin "2") (pinfunction "2_2") (pintype "passive"))
    )
    (net (code "136") (name "Net-(U3C-PC15-OSC32_OUT)") (class "Default")
      (node (ref "C105") (pin "1") (pinfunction "1_1") (pintype "passive"))
      (node (ref "U3") (pin "D1") (pinfunction "PC15-OSC32_OUT_D1") (pintype "passive"))
      (node (ref "Y4") (pin "1") (pinfunction "1_1") (pintype "passive"))
    )
    (net (code "137") (name "Net-(U3H-PH0-OSC_IN)") (class "Default")
      (node (ref "C261") (pin "1") (pinfunction "1_1") (pintype "passive"))
      (node (ref "U3") (pin "J1") (pinfunction "PH0-OSC_IN_J1") (pintype "passive"))
      (node (ref "Y3") (pin "1") (pinfunction "1_1") (pintype "passive"))
    )
    (net (code "138") (name "Net-(U3H-PH1-OSC_OUT)") (class "Default")
      (node (ref "C264") (pin "1") (pinfunction "1_1") (pintype "passive"))
      (node (ref "U3") (pin "J2") (pinfunction "PH1-OSC_OUT_J2") (pintype "passive"))
      (node (ref "Y3") (pin "3") (pinfunction "3_3") (pintype "passive"))
    )
    (net (code "139") (name "Net-(U3J-PJ7)") (class "Default")
      (node (ref "LOVE") (pin "X") (pinfunction "X_X") (pintype "passive"))
      (node (ref "U3") (pin "R9") (pinfunction "PJ7_R9") (pintype "passive"))
    )
    (net (code "140") (name "Net-(U3L-BOOT0)") (class "Default")
      (node (ref "R385") (pin "2") (pinfunction "2_2") (pintype "passive"))
      (node (ref "U3") (pin "B6") (pinfunction "BOOT0_B6") (pintype "passive"))
    )
    (net (code "141") (name "Net-(U3L-NRST)") (class "Default")
      (node (ref "R384") (pin "2") (pinfunction "2_2") (pintype "passive"))
      (node (ref "U3") (pin "J5") (pinfunction "NRST_J5") (pintype "passive"))
    )
    (net (code "142") (name "Net-(U3L-OTG_HS_DM)") (class "Default")
      (node (ref "R383") (pin "2") (pinfunction "2_2") (pintype "passive"))
      (node (ref "U3") (pin "H15") (pinfunction "OTG_HS_DM_H15") (pintype "passive"))
    )
    (net (code "143") (name "Net-(U3L-OTG_HS_DP)") (class "Default")
      (node (ref "R382") (pin "2") (pinfunction "2_2") (pintype "passive"))
      (node (ref "U3") (pin "G15") (pinfunction "OTG_HS_DP_G15") (pintype "passive"))
    )
    (net (code "144") (name "Net-(U3M-VDD11USB)") (class "Default")
      (node (ref "C286") (pin "1") (pinfunction "1_1") (pintype "passive"))
      (node (ref "C287") (pin "1") (pinfunction "1_1") (pintype "passive"))
      (node (ref "L21") (pin "1") (pinfunction "1_1") (pintype "passive"))
      (node (ref "U3") (pin "E6") (pinfunction "VCAP_E6") (pintype "passive"))
      (node (ref "U3") (pin "H12") (pinfunction "VDD11USB_H12") (pintype "passive"))
      (node (ref "U3") (pin "L10") (pinfunction "VCAP_L10") (pintype "passive"))
    )
    (net (code "145") (name "Net-(U3M-VDDA)") (class "Default")
      (node (ref "C106") (pin "2") (pinfunction "2_2") (pintype "passive"))
      (node (ref "C281") (pin "2") (pinfunction "2_2") (pintype "passive"))
      (node (ref "L6") (pin "2") (pinfunction "2_2") (pintype "passive"))
      (node (ref "U3") (pin "L3") (pinfunction "VDDA_L3") (pintype "passive"))
    )
    (net (code "146") (name "Net-(U3M-VDDIO2)") (class "Default")
      (node (ref "C277") (pin "2") (pinfunction "2_2") (pintype "passive"))
      (node (ref "C65") (pin "2") (pinfunction "2_2") (pintype "passive"))
      (node (ref "R218") (pin "2") (pinfunction "2_2") (pintype "passive"))
      (node (ref "R351") (pin "2") (pinfunction "2_2") (pintype "passive"))
      (node (ref "U3") (pin "D7") (pinfunction "VDDIO2_D7") (pintype "passive"))
    )
    (net (code "147") (name "Net-(U3M-VDDSMPS)") (class "Default")
      (node (ref "C288") (pin "1") (pinfunction "1_1") (pintype "passive"))
      (node (ref "C64") (pin "1") (pinfunction "1_1") (pintype "passive"))
      (node (ref "R434") (pin "2") (pinfunction "2_2") (pintype "passive"))
      (node (ref "U3") (pin "R13") (pinfunction "VDDSMPS_R13") (pintype "passive"))
    )
    (net (code "148") (name "Net-(U3M-VDDUSB)") (class "Default")
      (node (ref "C108") (pin "2") (pinfunction "2_2") (pintype "passive"))
      (node (ref "C279") (pin "2") (pinfunction "2_2") (pintype "passive"))
      (node (ref "R435") (pin "2") (pinfunction "2_2") (pintype "passive"))
      (node (ref "U3") (pin "F11") (pinfunction "VDDUSB_F11") (pintype "passive"))
    )
    (net (code "149") (name "Net-(U3M-VLXSMPS)") (class "Default")
      (node (ref "C285") (pin "2") (pinfunction "2_2") (pintype "passive"))
      (node (ref "L21") (pin "2") (pinfunction "2_2") (pintype "passive"))
      (node (ref "U3") (pin "R12") (pinfunction "VLXSMPS_R12") (pintype "passive"))
    )
    (net (code "150") (name "SOM_VREG_MDPX3_1P8") (class "Default")
      (node (ref "R351") (pin "1") (pinfunction "1_1") (pintype "passive"))
    )
    (net (code "151") (name "VBAT") (class "Default")
      (node (ref "C282") (pin "2") (pinfunction "2_2") (pintype "passive"))
      (node (ref "C63") (pin "2") (pinfunction "2_2") (pintype "passive"))
      (node (ref "U3") (pin "D3") (pinfunction "VBAT_D3") (pintype "passive"))
    )
    (net (code "152") (name "unconnected-(U3A-PA3-PadM4)") (class "Default")
      (node (ref "U3") (pin "M4") (pinfunction "PA3_M4") (pintype "passive+no_connect"))
    )
    (net (code "153") (name "unconnected-(U3C-PC4-PadN4)") (class "Default")
      (node (ref "U3") (pin "N4") (pinfunction "PC4_N4") (pintype "passive+no_connect"))
    )
    (net (code "154") (name "unconnected-(U3C-PC5-PadM5)") (class "Default")
      (node (ref "U3") (pin "M5") (pinfunction "PC5_M5") (pintype "passive+no_connect"))
    )
    (net (code "155") (name "unconnected-(U3C-PC13-PadC3)") (class "Default")
      (node (ref "U3") (pin "C3") (pinfunction "PC13_C3") (pintype "passive+no_connect"))
    )
    (net (code "156") (name "unconnected-(U3D-PD2-PadD11)") (class "Default")
      (node (ref "U3") (pin "D11") (pinfunction "PD2_D11") (pintype "passive+no_connect"))
    )
    (net (code "157") (name "unconnected-(U3D-PD4-PadB13)") (class "Default")
      (node (ref "U3") (pin "B13") (pinfunction "PD4_B13") (pintype "passive+no_connect"))
    )
    (net (code "158") (name "unconnected-(U3D-PD6-PadA10)") (class "Default")
      (node (ref "U3") (pin "A10") (pinfunction "PD6_A10") (pintype "passive+no_connect"))
    )
    (net (code "159") (name "unconnected-(U3D-PD7-PadC9)") (class "Default")
      (node (ref "U3") (pin "C9") (pinfunction "PD7_C9") (pintype "passive+no_connect"))
    )
    (net (code "160") (name "unconnected-(U3D-PD8-PadL12)") (class "Default")
      (node (ref "U3") (pin "L12") (pinfunction "PD8_L12") (pintype "passive+no_connect"))
    )
    (net (code "161") (name "unconnected-(U3E-PE0-PadD6)") (class "Default")
      (node (ref "U3") (pin "D6") (pinfunction "PE0_D6") (pintype "passive+no_connect"))
    )
    (net (code "162") (name "unconnected-(U3E-PE9-PadN8)") (class "Default")
      (node (ref "U3") (pin "N8") (pinfunction "PE9_N8") (pintype "passive+no_connect"))
    )
    (net (code "163") (name "unconnected-(U3E-PE10-PadM9)") (class "Default")
      (node (ref "U3") (pin "M9") (pinfunction "PE10_M9") (pintype "passive+no_connect"))
    )
    (net (code "164") (name "unconnected-(U3E-PE11-PadR10)") (class "Default")
      (node (ref "U3") (pin "R10") (pinfunction "PE11_R10") (pintype "passive+no_connect"))
    )
    (net (code "165") (name "unconnected-(U3F-PF2-PadF2)") (class "Default")
      (node (ref "U3") (pin "F2") (pinfunction "PF2_F2") (pintype "passive+no_connect"))
    )
    (net (code "166") (name "unconnected-(U3F-PF3-PadH5)") (class "Default")
      (node (ref "U3") (pin "H5") (pinfunction "PF3_H5") (pintype "passive+no_connect"))
    )
    (net (code "167") (name "unconnected-(U3F-PF5-PadH4)") (class "Default")
      (node (ref "U3") (pin "H4") (pinfunction "PF5_H4") (pintype "passive"))
    )
    (net (code "168") (name "unconnected-(U3F-PF8-PadH1)") (class "Default")
      (node (ref "U3") (pin "H1") (pinfunction "PF8_H1") (pintype "passive+no_connect"))
    )
    (net (code "169") (name "unconnected-(U3F-PF9-PadJ4)") (class "Default")
      (node (ref "U3") (pin "J4") (pinfunction "PF9_J4") (pintype "passive+no_connect"))
    )
    (net (code "170") (name "unconnected-(U3F-PF10-PadK1)") (class "Default")
      (node (ref "U3") (pin "K1") (pinfunction "PF10_K1") (pintype "passive+no_connect"))
    )
    (net (code "171") (name "unconnected-(U3F-PF11-PadL7)") (class "Default")
      (node (ref "U3") (pin "L7") (pinfunction "PF11_L7") (pintype "passive+no_connect"))
    )
    (net (code "172") (name "unconnected-(U3F-PF12-PadP6)") (class "Default")
      (node (ref "U3") (pin "P6") (pinfunction "PF12_P6") (pintype "passive+no_connect"))
    )
    (net (code "173") (name "unconnected-(U3F-PF13-PadR6)") (class "Default")
      (node (ref "U3") (pin "R6") (pinfunction "PF13_R6") (pintype "passive+no_connect"))
    )
    (net (code "174") (name "unconnected-(U3F-PF15-PadN7)") (class "Default")
      (node (ref "U3") (pin "N7") (pinfunction "PF15_N7") (pintype "passive+no_connect"))
    )
    (net (code "175") (name "unconnected-(U3G-PG0-PadP7)") (class "Default")
      (node (ref "U3") (pin "P7") (pinfunction "PG0_P7") (pintype "passive+no_connect"))
    )
    (net (code "176") (name "unconnected-(U3G-PG1-PadR7)") (class "Default")
      (node (ref "U3") (pin "R7") (pinfunction "PG1_R7") (pintype "passive+no_connect"))
    )
    (net (code "177") (name "unconnected-(U3G-PG7-PadH11)") (class "Default")
      (node (ref "U3") (pin "H11") (pinfunction "PG7_H11") (pintype "passive+no_connect"))
    )
    (net (code "178") (name "unconnected-(U3I-PI0-PadE12)") (class "Default")
      (node (ref "U3") (pin "E12") (pinfunction "PI0_E12") (pintype "passive"))
    )
    (net (code "179") (name "unconnected-(U3I-PI1-PadD15)") (class "Default")
      (node (ref "U3") (pin "D15") (pinfunction "PI1_D15") (pintype "passive+no_connect"))
    )
    (net (code "180") (name "unconnected-(U3I-PI3-PadD14)") (class "Default")
      (node (ref "U3") (pin "D14") (pinfunction "PI3_D14") (pintype "passive+no_connect"))
    )
    (net (code "181") (name "unconnected-(U3I-PI4-PadC5)") (class "Default")
      (node (ref "U3") (pin "C5") (pinfunction "PI4_C5") (pintype "passive+no_connect"))
    )
    (net (code "182") (name "unconnected-(U3I-PI6-PadA3)") (class "Default")
      (node (ref "U3") (pin "A3") (pinfunction "PI6_A3") (pintype "passive+no_connect"))
    )
    (net (code "183") (name "unconnected-(U3I-PI10-PadC1)") (class "Default")
      (node (ref "U3") (pin "C1") (pinfunction "PI10_C1") (pintype "passive+no_connect"))
    )
    (net (code "184") (name "unconnected-(U3I-PI12-PadF1)") (class "Default")
      (node (ref "U3") (pin "F1") (pinfunction "PI12_F1") (pintype "passive+no_connect"))
    )
    (net (code "185") (name "unconnected-(U3I-PI13-PadG3)") (class "Default")
      (node (ref "U3") (pin "G3") (pinfunction "PI13_G3") (pintype "passive+no_connect"))
    )
    (net (code "186") (name "unconnected-(U3I-PI14-PadG2)") (class "Default")
      (node (ref "U3") (pin "G2") (pinfunction "PI14_G2") (pintype "passive+no_connect"))
    )
    (net (code "187") (name "unconnected-(U3I-PI15-PadN5)") (class "Default")
      (node (ref "U3") (pin "N5") (pinfunction "PI15_N5") (pintype "passive+no_connect"))
    )
    (net (code "188") (name "unconnected-(U3J-PJ0-PadR4)") (class "Default")
      (node (ref "U3") (pin "R4") (pinfunction "PJ0_R4") (pintype "passive+no_connect"))
    )
    (net (code "189") (name "unconnected-(U3J-PJ1-PadM6)") (class "Default")
      (node (ref "U3") (pin "M6") (pinfunction "PJ1_M6") (pintype "passive+no_connect"))
    )
    (net (code "190") (name "unconnected-(U3J-PJ2-PadP5)") (class "Default")
      (node (ref "U3") (pin "P5") (pinfunction "PJ2_P5") (pintype "passive+no_connect"))
    )
    (net (code "191") (name "unconnected-(U3J-PJ3-PadR5)") (class "Default")
      (node (ref "U3") (pin "R5") (pinfunction "PJ3_R5") (pintype "passive+no_connect"))
    )
    (net (code "192") (name "unconnected-(U3J-PJ4-PadN6)") (class "Default")
      (node (ref "U3") (pin "N6") (pinfunction "PJ4_N6") (pintype "passive+no_connect"))
    )
    (net (code "193") (name "unconnected-(U3J-PJ5-PadP8)") (class "Default")
      (node (ref "U3") (pin "P8") (pinfunction "PJ5_P8") (pintype "passive+no_connect"))
    )
    (net (code "194") (name "unconnected-(U3J-PJ6-PadR8)") (class "Default")
      (node (ref "U3") (pin "R8") (pinfunction "PJ6_R8") (pintype "passive+no_connect"))
    )
    (net (code "195") (name "unconnected-(U3J-PJ8-PadP9)") (class "Default")
      (node (ref "U3") (pin "P9") (pinfunction "PJ8_P9") (pintype "passive+no_connect"))
    )
    (net (code "196") (name "unconnected-(U3J-PJ9-PadN9)") (class "Default")
      (node (ref "U3") (pin "N9") (pinfunction "PJ9_N9") (pintype "passive+no_connect"))
    )
    (net (code "197") (name "unconnected-(U3J-PJ10-PadD13)") (class "Default")
      (node (ref "U3") (pin "D13") (pinfunction "PJ10_D13") (pintype "passive+no_connect"))
    )
    (net (code "198") (name "unconnected-(U3J-PJ11-PadC14)") (class "Default")
      (node (ref "U3") (pin "C14") (pinfunction "PJ11_C14") (pintype "passive+no_connect"))
    )
    (net (code "199") (name "unconnected-(U3J-PJ12-PadA13)") (class "Default")
      (node (ref "U3") (pin "A13") (pinfunction "PJ12_A13") (pintype "passive+no_connect"))
    )
    (net (code "200") (name "unconnected-(U3J-PJ13-PadC11)") (class "Default")
      (node (ref "U3") (pin "C11") (pinfunction "PJ13_C11") (pintype "passive+no_connect"))
    )
    (net (code "201") (name "unconnected-(U3J-PJ14-PadD10)") (class "Default")
      (node (ref "U3") (pin "D10") (pinfunction "PJ14_D10") (pintype "passive+no_connect"))
    )
    (net (code "202") (name "unconnected-(U3J-PJ15-PadE9)") (class "Default")
      (node (ref "U3") (pin "E9") (pinfunction "PJ15_E9") (pintype "passive+no_connect"))
    )
    (net (code "203") (name "unconnected-(U3K-PK3-PadA12)") (class "Default")
      (node (ref "U3") (pin "A12") (pinfunction "PK3_A12") (pintype "passive+no_connect"))
    )
    (net (code "204") (name "unconnected-(U3K-PK4-PadB11)") (class "Default")
      (node (ref "U3") (pin "B11") (pinfunction "PK4_B11") (pintype "passive+no_connect"))
    )
    (net (code "205") (name "unconnected-(U3K-PK5-PadC10)") (class "Default")
      (node (ref "U3") (pin "C10") (pinfunction "PK5_C10") (pintype "passive+no_connect"))
    )
    (net (code "206") (name "unconnected-(U3K-PK6-PadA11)") (class "Default")
      (node (ref "U3") (pin "A11") (pinfunction "PK6_A11") (pintype "passive+no_connect"))
    )
    (net (code "207") (name "unconnected-(U3K-PK7-PadB10)") (class "Default")
      (node (ref "U3") (pin "B10") (pinfunction "PK7_B10") (pintype "passive+no_connect"))
    )
    (net (code "208") (name "unconnected-(U3K-PK8-PadD9)") (class "Default")
      (node (ref "U3") (pin "D9") (pinfunction "PK8_D9") (pintype "passive+no_connect"))
    )
    (net (code "209") (name "unconnected-(U3K-PK9-PadA2)") (class "Default")
      (node (ref "U3") (pin "A2") (pinfunction "PK9_A2") (pintype "passive+no_connect"))
    )
    (net (code "210") (name "unconnected-(U3K-PK12-PadF5)") (class "Default")
      (node (ref "U3") (pin "F5") (pinfunction "PK12_F5") (pintype "passive+no_connect"))
    )
    (net (code "211") (name "unconnected-(U3K-PK14-PadF4)") (class "Default")
      (node (ref "U3") (pin "F4") (pinfunction "PK14_F4") (pintype "passive+no_connect"))
    )
    (net (code "212") (name "unconnected-(U3K-PK15-PadG5)") (class "Default")
      (node (ref "U3") (pin "G5") (pinfunction "PK15_G5") (pintype "passive+no_connect"))
    )
  )
)
